# balise_r_ceptrice_-_partie_filtrage.net
KiCad netlist of a schematic drawn in EAGLE
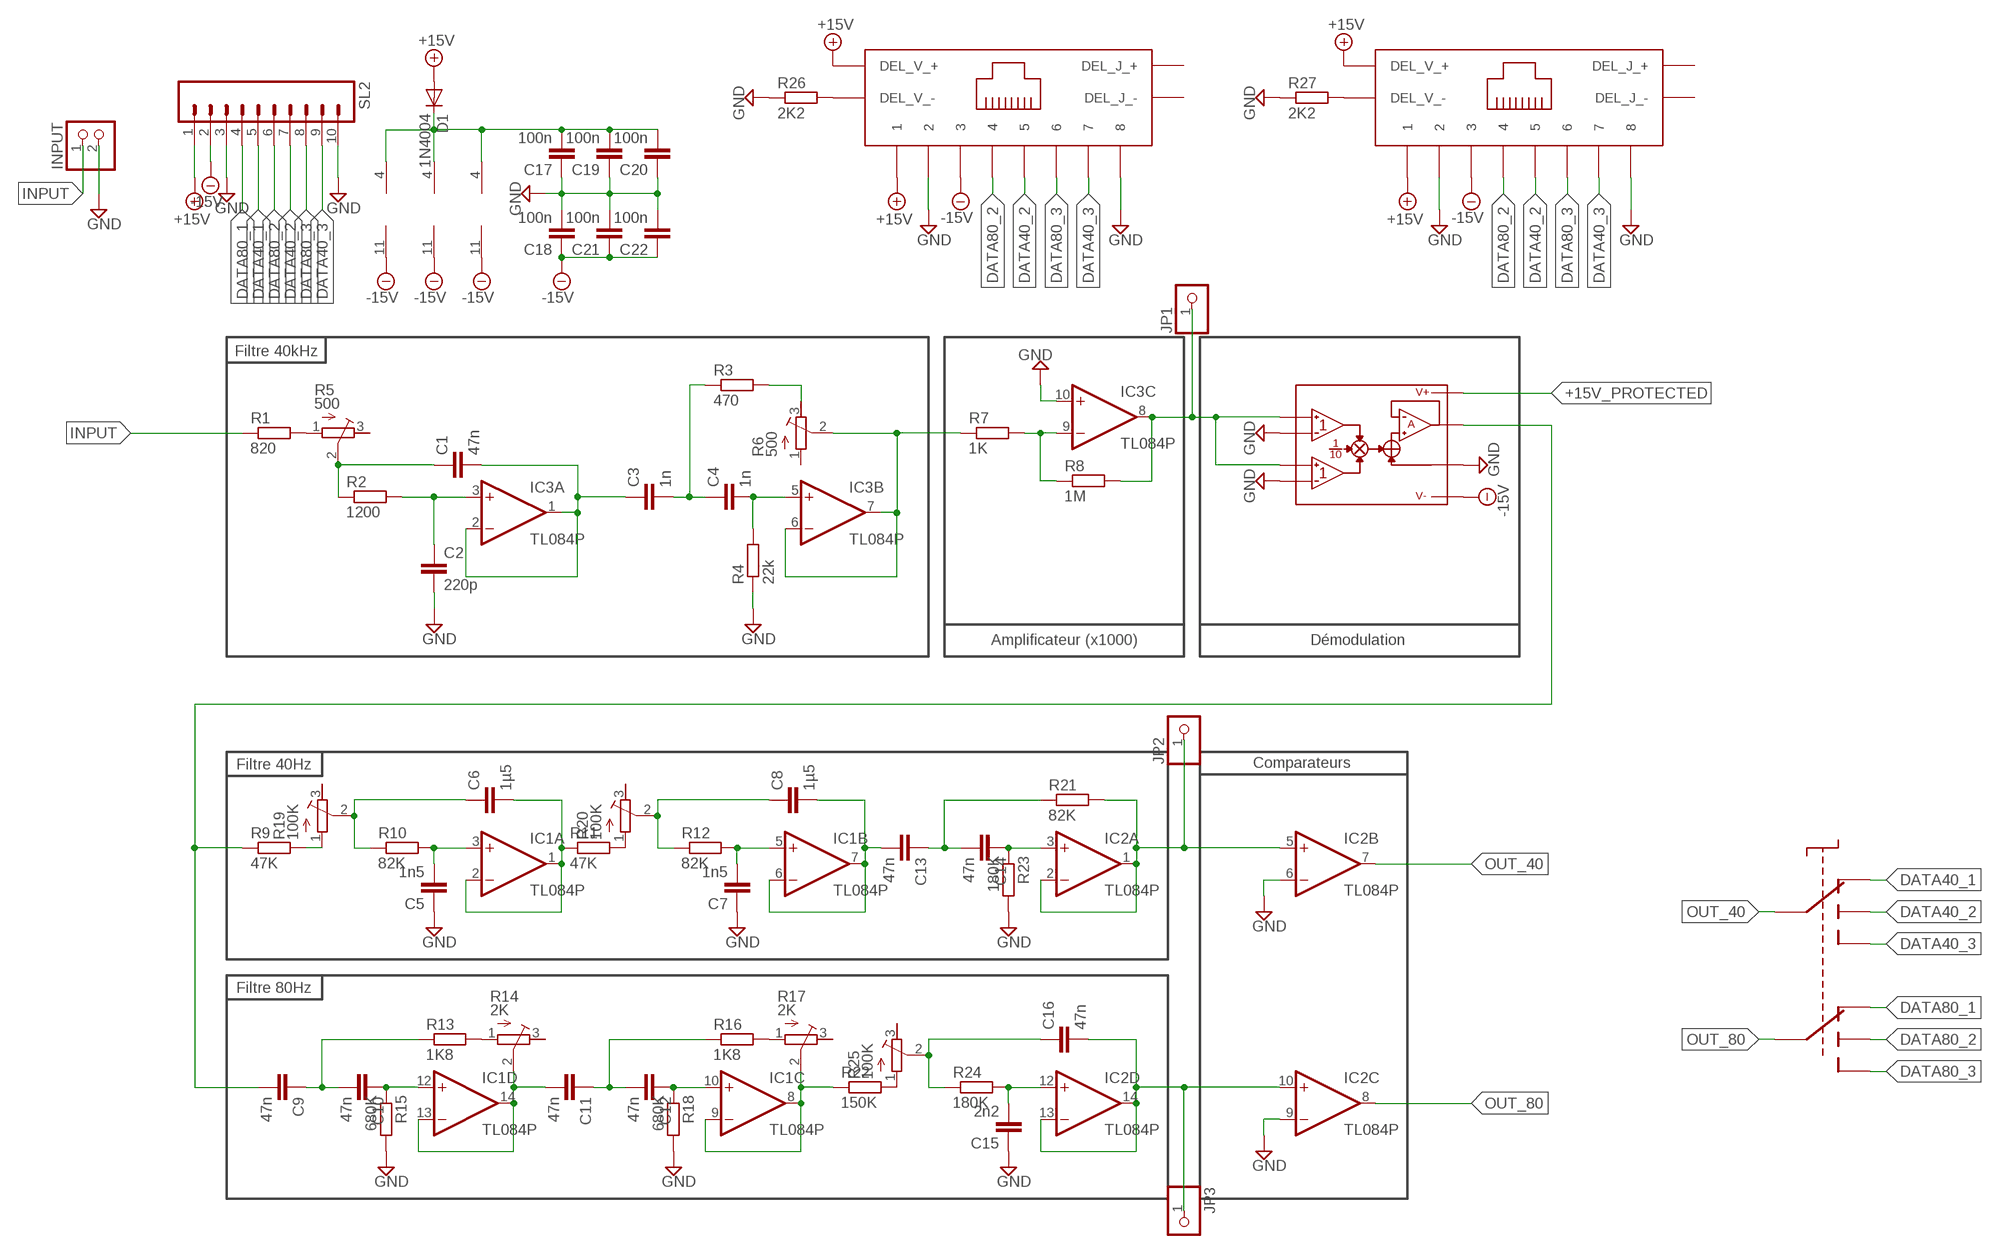
[diagram p0: schematic, sheet 1]

(export (version "E")
  (design (tool "Eeschema 10.0.6"))
  (components
    (comp (ref "C1")
      (value "47n")
      (footprint "eagle-import:C050-024X044")
      (libsource (lib "eagle-import") (part "C-EU050-024X044"))
    )
    (comp (ref "C2")
      (value "220p")
      (footprint "eagle-import:C050-024X044")
      (fields (field (name "MF") "SUSUMU") (field (name "MPN") "RR1220P-104-B-T5"))
      (libsource (lib "eagle-import") (part "C-EU050-024X044"))
    )
    (comp (ref "C3")
      (value "1n")
      (footprint "eagle-import:C050-024X044")
      (libsource (lib "eagle-import") (part "C-EU050-024X044"))
    )
    (comp (ref "C4")
      (value "1n")
      (footprint "eagle-import:C050-024X044")
      (libsource (lib "eagle-import") (part "C-EU050-024X044"))
    )
    (comp (ref "C5")
      (value "1n5")
      (footprint "eagle-import:C050-024X044")
      (libsource (lib "eagle-import") (part "C-EU050-024X044"))
    )
    (comp (ref "C6")
      (value "1µ5")
      (footprint "eagle-import:C150-091X182")
      (libsource (lib "eagle-import") (part "C-EU150-091X182"))
    )
    (comp (ref "C7")
      (value "1n5")
      (footprint "eagle-import:C050-024X044")
      (libsource (lib "eagle-import") (part "C-EU050-024X044"))
    )
    (comp (ref "C8")
      (value "1µ5")
      (footprint "eagle-import:C150-091X182")
      (libsource (lib "eagle-import") (part "C-EU150-091X182"))
    )
    (comp (ref "C9")
      (value "47n")
      (footprint "eagle-import:C050-024X044")
      (libsource (lib "eagle-import") (part "C-EU050-024X044"))
    )
    (comp (ref "C10")
      (value "47n")
      (footprint "eagle-import:C050-024X044")
      (libsource (lib "eagle-import") (part "C-EU050-024X044"))
    )
    (comp (ref "C11")
      (value "47n")
      (footprint "eagle-import:C050-024X044")
      (libsource (lib "eagle-import") (part "C-EU050-024X044"))
    )
    (comp (ref "C12")
      (value "47n")
      (footprint "eagle-import:C050-024X044")
      (libsource (lib "eagle-import") (part "C-EU050-024X044"))
    )
    (comp (ref "C13")
      (value "47n")
      (footprint "eagle-import:C050-024X044")
      (libsource (lib "eagle-import") (part "C-EU050-024X044"))
    )
    (comp (ref "C14")
      (value "47n")
      (footprint "eagle-import:C050-024X044")
      (libsource (lib "eagle-import") (part "C-EU050-024X044"))
    )
    (comp (ref "C15")
      (value "2n2")
      (footprint "eagle-import:C050-024X044")
      (libsource (lib "eagle-import") (part "C-EU050-024X044"))
    )
    (comp (ref "C16")
      (value "47n")
      (footprint "eagle-import:C050-024X044")
      (libsource (lib "eagle-import") (part "C-EU050-024X044"))
    )
    (comp (ref "C17")
      (value "100n")
      (footprint "eagle-import:C050-024X044")
      (libsource (lib "eagle-import") (part "C-EU050-024X044"))
    )
    (comp (ref "C18")
      (value "100n")
      (footprint "eagle-import:C050-024X044")
      (libsource (lib "eagle-import") (part "C-EU050-024X044"))
    )
    (comp (ref "C19")
      (value "100n")
      (footprint "eagle-import:C050-024X044")
      (libsource (lib "eagle-import") (part "C-EU050-024X044"))
    )
    (comp (ref "C20")
      (value "100n")
      (footprint "eagle-import:C050-024X044")
      (libsource (lib "eagle-import") (part "C-EU050-024X044"))
    )
    (comp (ref "C21")
      (value "100n")
      (footprint "eagle-import:C050-024X044")
      (libsource (lib "eagle-import") (part "C-EU050-024X044"))
    )
    (comp (ref "C22")
      (value "100n")
      (footprint "eagle-import:C050-024X044")
      (libsource (lib "eagle-import") (part "C-EU050-024X044"))
    )
    (comp (ref "D1")
      (value "1N4004")
      (footprint "eagle-import:DO41-10")
      (libsource (lib "eagle-import") (part "1N4004"))
    )
    (comp (ref "IC1")
      (value "TL084P")
      (footprint "eagle-import:DIL14")
      (fields (field (name "OC_FARNELL") "unknown"))
      (libsource (lib "eagle-import") (part "TL084P"))
    )
    (comp (ref "IC2")
      (value "TL084P")
      (footprint "eagle-import:DIL14")
      (fields (field (name "OC_FARNELL") "unknown"))
      (libsource (lib "eagle-import") (part "TL084P"))
    )
    (comp (ref "IC3")
      (value "TL084P")
      (footprint "eagle-import:DIL14")
      (fields (field (name "OC_FARNELL") "unknown"))
      (libsource (lib "eagle-import") (part "TL084P"))
    )
    (comp (ref "INPUT")
      (value "PINHD-1X2")
      (footprint "eagle-import:1X02")
      (libsource (lib "eagle-import") (part "PINHD-1X2"))
    )
    (comp (ref "JP1")
      (value "PINHD-1X1")
      (footprint "eagle-import:1X01")
      (libsource (lib "eagle-import") (part "PINHD-1X1"))
    )
    (comp (ref "JP2")
      (value "PINHD-1X1")
      (footprint "eagle-import:1X01")
      (libsource (lib "eagle-import") (part "PINHD-1X1"))
    )
    (comp (ref "JP3")
      (value "PINHD-1X1")
      (footprint "eagle-import:1X01")
      (libsource (lib "eagle-import") (part "PINHD-1X1"))
    )
    (comp (ref "R1")
      (value "820")
      (footprint "eagle-import:0207_2V")
      (libsource (lib "eagle-import") (part "R-EU_0207/2V"))
    )
    (comp (ref "R2")
      (value "1200")
      (footprint "eagle-import:0207_2V")
      (libsource (lib "eagle-import") (part "R-EU_0207/2V"))
    )
    (comp (ref "R3")
      (value "470")
      (footprint "eagle-import:0207_2V")
      (libsource (lib "eagle-import") (part "R-EU_0207/2V"))
    )
    (comp (ref "R4")
      (value "22k")
      (footprint "eagle-import:0207_2V")
      (libsource (lib "eagle-import") (part "R-EU_0207/2V"))
    )
    (comp (ref "R5")
      (value "500")
      (footprint "eagle-import:RTRIM3339P")
      (libsource (lib "eagle-import") (part "R-TRIMM3339P"))
    )
    (comp (ref "R6")
      (value "500")
      (footprint "eagle-import:RTRIM3339P")
      (libsource (lib "eagle-import") (part "R-TRIMM3339P"))
    )
    (comp (ref "R7")
      (value "1K")
      (footprint "eagle-import:0204_7")
      (libsource (lib "eagle-import") (part "R-EU_0204/7"))
    )
    (comp (ref "R8")
      (value "1M")
      (footprint "eagle-import:0204_7")
      (libsource (lib "eagle-import") (part "R-EU_0204/7"))
    )
    (comp (ref "R9")
      (value "47K")
      (footprint "eagle-import:0204_7")
      (libsource (lib "eagle-import") (part "R-EU_0204/7"))
    )
    (comp (ref "R10")
      (value "82K")
      (footprint "eagle-import:0204_7")
      (libsource (lib "eagle-import") (part "R-EU_0204/7"))
    )
    (comp (ref "R11")
      (value "47K")
      (footprint "eagle-import:0207_2V")
      (libsource (lib "eagle-import") (part "R-EU_0207/2V"))
    )
    (comp (ref "R12")
      (value "82K")
      (footprint "eagle-import:0207_2V")
      (libsource (lib "eagle-import") (part "R-EU_0207/2V"))
    )
    (comp (ref "R13")
      (value "1K8")
      (footprint "eagle-import:0207_2V")
      (libsource (lib "eagle-import") (part "R-EU_0207/2V"))
    )
    (comp (ref "R14")
      (value "2K")
      (footprint "eagle-import:RTRIM3339P")
      (libsource (lib "eagle-import") (part "R-TRIMM3339P"))
    )
    (comp (ref "R15")
      (value "680K")
      (footprint "eagle-import:0207_2V")
      (libsource (lib "eagle-import") (part "R-EU_0207/2V"))
    )
    (comp (ref "R16")
      (value "1K8")
      (footprint "eagle-import:0207_2V")
      (libsource (lib "eagle-import") (part "R-EU_0207/2V"))
    )
    (comp (ref "R17")
      (value "2K")
      (footprint "eagle-import:RTRIM3339P")
      (libsource (lib "eagle-import") (part "R-TRIMM3339P"))
    )
    (comp (ref "R18")
      (value "680K")
      (footprint "eagle-import:0207_2V")
      (libsource (lib "eagle-import") (part "R-EU_0207/2V"))
    )
    (comp (ref "R19")
      (value "100K")
      (footprint "eagle-import:RTRIM3339P")
      (libsource (lib "eagle-import") (part "R-TRIMM3339P"))
    )
    (comp (ref "R20")
      (value "100K")
      (footprint "eagle-import:RTRIM3339P")
      (libsource (lib "eagle-import") (part "R-TRIMM3339P"))
    )
    (comp (ref "R21")
      (value "82K")
      (footprint "eagle-import:0207_2V")
      (libsource (lib "eagle-import") (part "R-EU_0207/2V"))
    )
    (comp (ref "R22")
      (value "150K")
      (footprint "eagle-import:0207_2V")
      (libsource (lib "eagle-import") (part "R-EU_0207/2V"))
    )
    (comp (ref "R23")
      (value "180K")
      (footprint "eagle-import:0207_2V")
      (libsource (lib "eagle-import") (part "R-EU_0207/2V"))
    )
    (comp (ref "R24")
      (value "180K")
      (footprint "eagle-import:0207_2V")
      (libsource (lib "eagle-import") (part "R-EU_0207/2V"))
    )
    (comp (ref "R25")
      (value "100K")
      (footprint "eagle-import:RTRIM3339P")
      (libsource (lib "eagle-import") (part "R-TRIMM3339P"))
    )
    (comp (ref "R26")
      (value "2K2")
      (footprint "eagle-import:0207_2V")
      (libsource (lib "eagle-import") (part "R-EU_0207/2V"))
    )
    (comp (ref "R27")
      (value "2K2")
      (footprint "eagle-import:0207_2V")
      (libsource (lib "eagle-import") (part "R-EU_0207/2V"))
    )
    (comp (ref "SL2")
      (value "M10")
      (footprint "eagle-import:10P")
      (fields (field (name "OC_FARNELL") "unknown"))
      (libsource (lib "eagle-import") (part "M10"))
    )
    (comp (ref "U$1")
      (value "AD633JN")
      (footprint "eagle-import:DIL08")
      (libsource (lib "eagle-import") (part "AD633JN"))
    )
    (comp (ref "U$2")
      (value "RJ45_FEMELLE")
      (footprint "eagle-import:RJ45_FEMELLE")
      (libsource (lib "eagle-import") (part "RJ45_FEMELLE"))
    )
    (comp (ref "U$3")
      (value "RJ45_FEMELLE")
      (footprint "eagle-import:RJ45_FEMELLE")
      (libsource (lib "eagle-import") (part "RJ45_FEMELLE"))
    )
    (comp (ref "U$4")
      (value "SWITCH_DP3T_SP112")
      (footprint "eagle-import:SWITCH_SP112")
      (libsource (lib "eagle-import") (part "SWITCH_DP3T_SP112"))
    )
  )
  (nets
    (net (code "1") (name "+15V") (class "Default")
      (node (ref "D1") (pin "A") (pinfunction "A_A") (pintype "passive"))
      (node (ref "SL2") (pin "1") (pinfunction "1_1") (pintype "passive"))
      (node (ref "U$2") (pin "1") (pinfunction "1_1") (pintype "bidirectional"))
      (node (ref "U$2") (pin "DEL_V_+") (pinfunction "DEL_V_+_DEL_V_+") (pintype "bidirectional"))
      (node (ref "U$3") (pin "1") (pinfunction "1_1") (pintype "bidirectional"))
      (node (ref "U$3") (pin "DEL_V_+") (pinfunction "DEL_V_+_DEL_V_+") (pintype "bidirectional"))
    )
    (net (code "2") (name "+15V_PROTECTED") (class "Default")
      (node (ref "C17") (pin "2") (pinfunction "2_2") (pintype "passive"))
      (node (ref "C19") (pin "2") (pinfunction "2_2") (pintype "passive"))
      (node (ref "C20") (pin "2") (pinfunction "2_2") (pintype "passive"))
      (node (ref "D1") (pin "C") (pinfunction "C_C") (pintype "passive"))
      (node (ref "IC1") (pin "4") (pinfunction "V+_4") (pintype "power_in"))
      (node (ref "IC2") (pin "4") (pinfunction "V+_4") (pintype "power_in"))
      (node (ref "IC3") (pin "4") (pinfunction "V+_4") (pintype "power_in"))
      (node (ref "U$1") (pin "8") (pinfunction "+V_8") (pintype "bidirectional"))
    )
    (net (code "3") (name "-15V") (class "Default")
      (node (ref "C18") (pin "1") (pinfunction "1_1") (pintype "passive"))
      (node (ref "C21") (pin "1") (pinfunction "1_1") (pintype "passive"))
      (node (ref "C22") (pin "1") (pinfunction "1_1") (pintype "passive"))
      (node (ref "IC1") (pin "11") (pinfunction "V-_11") (pintype "power_in"))
      (node (ref "IC2") (pin "11") (pinfunction "V-_11") (pintype "power_in"))
      (node (ref "IC3") (pin "11") (pinfunction "V-_11") (pintype "power_in"))
      (node (ref "SL2") (pin "2") (pinfunction "2_2") (pintype "passive"))
      (node (ref "U$1") (pin "5") (pinfunction "-V_5") (pintype "bidirectional"))
      (node (ref "U$2") (pin "3") (pinfunction "3_3") (pintype "bidirectional"))
      (node (ref "U$3") (pin "3") (pinfunction "3_3") (pintype "bidirectional"))
    )
    (net (code "4") (name "DATA40_1") (class "Default")
      (node (ref "SL2") (pin "5") (pinfunction "5_5") (pintype "passive"))
      (node (ref "U$4") (pin "1A") (pinfunction "1A_1A") (pintype "bidirectional"))
    )
    (net (code "5") (name "DATA40_2") (class "Default")
      (node (ref "SL2") (pin "7") (pinfunction "7_7") (pintype "passive"))
      (node (ref "U$2") (pin "5") (pinfunction "5_5") (pintype "bidirectional"))
      (node (ref "U$3") (pin "5") (pinfunction "5_5") (pintype "bidirectional"))
      (node (ref "U$4") (pin "1B") (pinfunction "1B_1B") (pintype "bidirectional"))
    )
    (net (code "6") (name "DATA40_3") (class "Default")
      (node (ref "SL2") (pin "9") (pinfunction "9_9") (pintype "passive"))
      (node (ref "U$2") (pin "7") (pinfunction "7_7") (pintype "bidirectional"))
      (node (ref "U$3") (pin "7") (pinfunction "7_7") (pintype "bidirectional"))
      (node (ref "U$4") (pin "1C") (pinfunction "1C_1C") (pintype "bidirectional"))
    )
    (net (code "7") (name "DATA80_1") (class "Default")
      (node (ref "SL2") (pin "4") (pinfunction "4_4") (pintype "passive"))
      (node (ref "U$4") (pin "2A") (pinfunction "2A_2A") (pintype "bidirectional"))
    )
    (net (code "8") (name "DATA80_2") (class "Default")
      (node (ref "SL2") (pin "6") (pinfunction "6_6") (pintype "passive"))
      (node (ref "U$2") (pin "4") (pinfunction "4_4") (pintype "bidirectional"))
      (node (ref "U$3") (pin "4") (pinfunction "4_4") (pintype "bidirectional"))
      (node (ref "U$4") (pin "2B") (pinfunction "2B_2B") (pintype "bidirectional"))
    )
    (net (code "9") (name "DATA80_3") (class "Default")
      (node (ref "SL2") (pin "8") (pinfunction "8_8") (pintype "passive"))
      (node (ref "U$2") (pin "6") (pinfunction "6_6") (pintype "bidirectional"))
      (node (ref "U$3") (pin "6") (pinfunction "6_6") (pintype "bidirectional"))
      (node (ref "U$4") (pin "2C") (pinfunction "2C_2C") (pintype "bidirectional"))
    )
    (net (code "10") (name "GND") (class "Default")
      (node (ref "C15") (pin "1") (pinfunction "1_1") (pintype "passive"))
      (node (ref "C17") (pin "1") (pinfunction "1_1") (pintype "passive"))
      (node (ref "C18") (pin "2") (pinfunction "2_2") (pintype "passive"))
      (node (ref "C19") (pin "1") (pinfunction "1_1") (pintype "passive"))
      (node (ref "C2") (pin "2") (pinfunction "2_2") (pintype "passive"))
      (node (ref "C20") (pin "1") (pinfunction "1_1") (pintype "passive"))
      (node (ref "C21") (pin "2") (pinfunction "2_2") (pintype "passive"))
      (node (ref "C22") (pin "2") (pinfunction "2_2") (pintype "passive"))
      (node (ref "C5") (pin "1") (pinfunction "1_1") (pintype "passive"))
      (node (ref "C7") (pin "1") (pinfunction "1_1") (pintype "passive"))
      (node (ref "IC2") (pin "6") (pinfunction "-IN_6") (pintype "input"))
      (node (ref "IC2") (pin "9") (pinfunction "-IN_9") (pintype "input"))
      (node (ref "IC3") (pin "10") (pinfunction "+IN_10") (pintype "input"))
      (node (ref "INPUT") (pin "2") (pinfunction "2_2") (pintype "passive"))
      (node (ref "R15") (pin "2") (pinfunction "2_2") (pintype "passive"))
      (node (ref "R18") (pin "2") (pinfunction "2_2") (pintype "passive"))
      (node (ref "R23") (pin "2") (pinfunction "2_2") (pintype "passive"))
      (node (ref "R26") (pin "1") (pinfunction "1_1") (pintype "passive"))
      (node (ref "R27") (pin "1") (pinfunction "1_1") (pintype "passive"))
      (node (ref "R4") (pin "1") (pinfunction "1_1") (pintype "passive"))
      (node (ref "SL2") (pin "10") (pinfunction "10_10") (pintype "passive"))
      (node (ref "SL2") (pin "3") (pinfunction "3_3") (pintype "passive"))
      (node (ref "U$1") (pin "2") (pinfunction "X2_2") (pintype "bidirectional"))
      (node (ref "U$1") (pin "4") (pinfunction "Y2_4") (pintype "bidirectional"))
      (node (ref "U$1") (pin "6") (pinfunction "Z_6") (pintype "bidirectional"))
      (node (ref "U$2") (pin "2") (pinfunction "2_2") (pintype "bidirectional"))
      (node (ref "U$2") (pin "8") (pinfunction "8_8") (pintype "bidirectional"))
      (node (ref "U$3") (pin "2") (pinfunction "2_2") (pintype "bidirectional"))
      (node (ref "U$3") (pin "8") (pinfunction "8_8") (pintype "bidirectional"))
    )
    (net (code "11") (name "INPUT") (class "Default")
      (node (ref "INPUT") (pin "1") (pinfunction "1_1") (pintype "passive"))
      (node (ref "R1") (pin "1") (pinfunction "1_1") (pintype "passive"))
    )
    (net (code "12") (name "Net-(C3-Pad2)") (class "Default")
      (node (ref "C3") (pin "2") (pinfunction "2_2") (pintype "passive"))
      (node (ref "C4") (pin "1") (pinfunction "1_1") (pintype "passive"))
      (node (ref "R3") (pin "1") (pinfunction "1_1") (pintype "passive"))
    )
    (net (code "13") (name "Net-(C10-Pad2)") (class "Default")
      (node (ref "C10") (pin "2") (pinfunction "2_2") (pintype "passive"))
      (node (ref "C9") (pin "1") (pinfunction "1_1") (pintype "passive"))
      (node (ref "R13") (pin "1") (pinfunction "1_1") (pintype "passive"))
    )
    (net (code "14") (name "Net-(C11-Pad1)") (class "Default")
      (node (ref "C11") (pin "1") (pinfunction "1_1") (pintype "passive"))
      (node (ref "C12") (pin "2") (pinfunction "2_2") (pintype "passive"))
      (node (ref "R16") (pin "1") (pinfunction "1_1") (pintype "passive"))
    )
    (net (code "15") (name "Net-(C13-Pad1)") (class "Default")
      (node (ref "C13") (pin "1") (pinfunction "1_1") (pintype "passive"))
      (node (ref "C14") (pin "2") (pinfunction "2_2") (pintype "passive"))
      (node (ref "R21") (pin "1") (pinfunction "1_1") (pintype "passive"))
    )
    (net (code "16") (name "Net-(IC1A-+IN)") (class "Default")
      (node (ref "C5") (pin "2") (pinfunction "2_2") (pintype "passive"))
      (node (ref "IC1") (pin "3") (pinfunction "+IN_3") (pintype "input"))
      (node (ref "R10") (pin "2") (pinfunction "2_2") (pintype "passive"))
    )
    (net (code "17") (name "Net-(IC1A--IN)") (class "Default")
      (node (ref "C6") (pin "2") (pinfunction "2_2") (pintype "passive"))
      (node (ref "IC1") (pin "1") (pinfunction "OUT_1") (pintype "output"))
      (node (ref "IC1") (pin "2") (pinfunction "-IN_2") (pintype "input"))
      (node (ref "R11") (pin "1") (pinfunction "1_1") (pintype "passive"))
    )
    (net (code "18") (name "Net-(IC1B-+IN)") (class "Default")
      (node (ref "C7") (pin "2") (pinfunction "2_2") (pintype "passive"))
      (node (ref "IC1") (pin "5") (pinfunction "+IN_5") (pintype "input"))
      (node (ref "R12") (pin "2") (pinfunction "2_2") (pintype "passive"))
    )
    (net (code "19") (name "Net-(IC1B--IN)") (class "Default")
      (node (ref "C13") (pin "2") (pinfunction "2_2") (pintype "passive"))
      (node (ref "C8") (pin "2") (pinfunction "2_2") (pintype "passive"))
      (node (ref "IC1") (pin "6") (pinfunction "-IN_6") (pintype "input"))
      (node (ref "IC1") (pin "7") (pinfunction "OUT_7") (pintype "output"))
    )
    (net (code "20") (name "Net-(IC1C-+IN)") (class "Default")
      (node (ref "C12") (pin "1") (pinfunction "1_1") (pintype "passive"))
      (node (ref "IC1") (pin "10") (pinfunction "+IN_10") (pintype "input"))
      (node (ref "R18") (pin "1") (pinfunction "1_1") (pintype "passive"))
    )
    (net (code "21") (name "Net-(IC1C--IN)") (class "Default")
      (node (ref "IC1") (pin "8") (pinfunction "OUT_8") (pintype "output"))
      (node (ref "IC1") (pin "9") (pinfunction "-IN_9") (pintype "input"))
      (node (ref "R17") (pin "2") (pinfunction "S_2") (pintype "passive"))
      (node (ref "R22") (pin "1") (pinfunction "1_1") (pintype "passive"))
    )
    (net (code "22") (name "Net-(IC1D-+IN)") (class "Default")
      (node (ref "C10") (pin "1") (pinfunction "1_1") (pintype "passive"))
      (node (ref "IC1") (pin "12") (pinfunction "+IN_12") (pintype "input"))
      (node (ref "R15") (pin "1") (pinfunction "1_1") (pintype "passive"))
    )
    (net (code "23") (name "Net-(IC1D--IN)") (class "Default")
      (node (ref "C11") (pin "2") (pinfunction "2_2") (pintype "passive"))
      (node (ref "IC1") (pin "13") (pinfunction "-IN_13") (pintype "input"))
      (node (ref "IC1") (pin "14") (pinfunction "OUT_14") (pintype "output"))
      (node (ref "R14") (pin "2") (pinfunction "S_2") (pintype "passive"))
    )
    (net (code "24") (name "Net-(IC2A-+IN)") (class "Default")
      (node (ref "C14") (pin "1") (pinfunction "1_1") (pintype "passive"))
      (node (ref "IC2") (pin "3") (pinfunction "+IN_3") (pintype "input"))
      (node (ref "R23") (pin "1") (pinfunction "1_1") (pintype "passive"))
    )
    (net (code "25") (name "Net-(IC2A--IN)") (class "Default")
      (node (ref "IC2") (pin "1") (pinfunction "OUT_1") (pintype "output"))
      (node (ref "IC2") (pin "2") (pinfunction "-IN_2") (pintype "input"))
      (node (ref "IC2") (pin "5") (pinfunction "+IN_5") (pintype "input"))
      (node (ref "JP2") (pin "1") (pinfunction "1_1") (pintype "passive"))
      (node (ref "R21") (pin "2") (pinfunction "2_2") (pintype "passive"))
    )
    (net (code "26") (name "Net-(IC2C-+IN)") (class "Default")
      (node (ref "C16") (pin "2") (pinfunction "2_2") (pintype "passive"))
      (node (ref "IC2") (pin "10") (pinfunction "+IN_10") (pintype "input"))
      (node (ref "IC2") (pin "13") (pinfunction "-IN_13") (pintype "input"))
      (node (ref "IC2") (pin "14") (pinfunction "OUT_14") (pintype "output"))
      (node (ref "JP3") (pin "1") (pinfunction "1_1") (pintype "passive"))
    )
    (net (code "27") (name "Net-(IC2D-+IN)") (class "Default")
      (node (ref "C15") (pin "2") (pinfunction "2_2") (pintype "passive"))
      (node (ref "IC2") (pin "12") (pinfunction "+IN_12") (pintype "input"))
      (node (ref "R24") (pin "2") (pinfunction "2_2") (pintype "passive"))
    )
    (net (code "28") (name "Net-(IC3A-+IN)") (class "Default")
      (node (ref "C2") (pin "1") (pinfunction "1_1") (pintype "passive"))
      (node (ref "IC3") (pin "3") (pinfunction "+IN_3") (pintype "input"))
      (node (ref "R2") (pin "2") (pinfunction "2_2") (pintype "passive"))
    )
    (net (code "29") (name "Net-(IC3A--IN)") (class "Default")
      (node (ref "C1") (pin "2") (pinfunction "2_2") (pintype "passive"))
      (node (ref "C3") (pin "1") (pinfunction "1_1") (pintype "passive"))
      (node (ref "IC3") (pin "1") (pinfunction "OUT_1") (pintype "output"))
      (node (ref "IC3") (pin "2") (pinfunction "-IN_2") (pintype "input"))
    )
    (net (code "30") (name "Net-(IC3B-+IN)") (class "Default")
      (node (ref "C4") (pin "2") (pinfunction "2_2") (pintype "passive"))
      (node (ref "IC3") (pin "5") (pinfunction "+IN_5") (pintype "input"))
      (node (ref "R4") (pin "2") (pinfunction "2_2") (pintype "passive"))
    )
    (net (code "31") (name "Net-(IC3B--IN)") (class "Default")
      (node (ref "IC3") (pin "6") (pinfunction "-IN_6") (pintype "input"))
      (node (ref "IC3") (pin "7") (pinfunction "OUT_7") (pintype "output"))
      (node (ref "R6") (pin "2") (pinfunction "S_2") (pintype "passive"))
      (node (ref "R7") (pin "1") (pinfunction "1_1") (pintype "passive"))
    )
    (net (code "32") (name "Net-(IC3C--IN)") (class "Default")
      (node (ref "IC3") (pin "9") (pinfunction "-IN_9") (pintype "input"))
      (node (ref "R7") (pin "2") (pinfunction "2_2") (pintype "passive"))
      (node (ref "R8") (pin "1") (pinfunction "1_1") (pintype "passive"))
    )
    (net (code "33") (name "Net-(IC3C-OUT)") (class "Default")
      (node (ref "IC3") (pin "8") (pinfunction "OUT_8") (pintype "output"))
      (node (ref "JP1") (pin "1") (pinfunction "1_1") (pintype "passive"))
      (node (ref "R8") (pin "2") (pinfunction "2_2") (pintype "passive"))
      (node (ref "U$1") (pin "1") (pinfunction "X1_1") (pintype "bidirectional"))
      (node (ref "U$1") (pin "3") (pinfunction "Y1_3") (pintype "bidirectional"))
    )
    (net (code "34") (name "Net-(R5-E)") (class "Default")
      (node (ref "R1") (pin "2") (pinfunction "2_2") (pintype "passive"))
      (node (ref "R5") (pin "1") (pinfunction "E_1") (pintype "passive"))
    )
    (net (code "35") (name "Net-(R5-S)") (class "Default")
      (node (ref "C1") (pin "1") (pinfunction "1_1") (pintype "passive"))
      (node (ref "R2") (pin "1") (pinfunction "1_1") (pintype "passive"))
      (node (ref "R5") (pin "2") (pinfunction "S_2") (pintype "passive"))
    )
    (net (code "36") (name "Net-(R6-A)") (class "Default")
      (node (ref "R3") (pin "2") (pinfunction "2_2") (pintype "passive"))
      (node (ref "R6") (pin "3") (pinfunction "A_3") (pintype "passive"))
    )
    (net (code "37") (name "Net-(R14-E)") (class "Default")
      (node (ref "R13") (pin "2") (pinfunction "2_2") (pintype "passive"))
      (node (ref "R14") (pin "1") (pinfunction "E_1") (pintype "passive"))
    )
    (net (code "38") (name "Net-(R17-E)") (class "Default")
      (node (ref "R16") (pin "2") (pinfunction "2_2") (pintype "passive"))
      (node (ref "R17") (pin "1") (pinfunction "E_1") (pintype "passive"))
    )
    (net (code "39") (name "Net-(R19-E)") (class "Default")
      (node (ref "R19") (pin "1") (pinfunction "E_1") (pintype "passive"))
      (node (ref "R9") (pin "2") (pinfunction "2_2") (pintype "passive"))
    )
    (net (code "40") (name "Net-(R19-S)") (class "Default")
      (node (ref "C6") (pin "1") (pinfunction "1_1") (pintype "passive"))
      (node (ref "R10") (pin "1") (pinfunction "1_1") (pintype "passive"))
      (node (ref "R19") (pin "2") (pinfunction "S_2") (pintype "passive"))
    )
    (net (code "41") (name "Net-(R20-E)") (class "Default")
      (node (ref "R11") (pin "2") (pinfunction "2_2") (pintype "passive"))
      (node (ref "R20") (pin "1") (pinfunction "E_1") (pintype "passive"))
    )
    (net (code "42") (name "Net-(R20-S)") (class "Default")
      (node (ref "C8") (pin "1") (pinfunction "1_1") (pintype "passive"))
      (node (ref "R12") (pin "1") (pinfunction "1_1") (pintype "passive"))
      (node (ref "R20") (pin "2") (pinfunction "S_2") (pintype "passive"))
    )
    (net (code "43") (name "Net-(R25-E)") (class "Default")
      (node (ref "R22") (pin "2") (pinfunction "2_2") (pintype "passive"))
      (node (ref "R25") (pin "1") (pinfunction "E_1") (pintype "passive"))
    )
    (net (code "44") (name "Net-(R25-S)") (class "Default")
      (node (ref "C16") (pin "1") (pinfunction "1_1") (pintype "passive"))
      (node (ref "R24") (pin "1") (pinfunction "1_1") (pintype "passive"))
      (node (ref "R25") (pin "2") (pinfunction "S_2") (pintype "passive"))
    )
    (net (code "45") (name "Net-(R26-Pad2)") (class "Default")
      (node (ref "R26") (pin "2") (pinfunction "2_2") (pintype "passive"))
      (node (ref "U$2") (pin "DEL_V_-") (pinfunction "DEL_V_-_DEL_V_-") (pintype "bidirectional"))
    )
    (net (code "46") (name "Net-(R27-Pad2)") (class "Default")
      (node (ref "R27") (pin "2") (pinfunction "2_2") (pintype "passive"))
      (node (ref "U$3") (pin "DEL_V_-") (pinfunction "DEL_V_-_DEL_V_-") (pintype "bidirectional"))
    )
    (net (code "47") (name "Net-(U$1-W)") (class "Default")
      (node (ref "C9") (pin "2") (pinfunction "2_2") (pintype "passive"))
      (node (ref "R9") (pin "1") (pinfunction "1_1") (pintype "passive"))
      (node (ref "U$1") (pin "7") (pinfunction "W_7") (pintype "bidirectional"))
    )
    (net (code "48") (name "OUT_40") (class "Default")
      (node (ref "IC2") (pin "7") (pinfunction "OUT_7") (pintype "output"))
      (node (ref "U$4") (pin "COM_1") (pinfunction "COM1_COM_1") (pintype "bidirectional"))
    )
    (net (code "49") (name "OUT_80") (class "Default")
      (node (ref "IC2") (pin "8") (pinfunction "OUT_8") (pintype "output"))
      (node (ref "U$4") (pin "COM_2") (pinfunction "COM2_COM_2") (pintype "bidirectional"))
    )
    (net (code "50") (name "unconnected-(R5-A-Pad3)") (class "Default")
      (node (ref "R5") (pin "3") (pinfunction "A_3") (pintype "passive"))
    )
    (net (code "51") (name "unconnected-(R6-E-Pad1)") (class "Default")
      (node (ref "R6") (pin "1") (pinfunction "E_1") (pintype "passive"))
    )
    (net (code "52") (name "unconnected-(R14-A-Pad3)") (class "Default")
      (node (ref "R14") (pin "3") (pinfunction "A_3") (pintype "passive"))
    )
    (net (code "53") (name "unconnected-(R17-A-Pad3)") (class "Default")
      (node (ref "R17") (pin "3") (pinfunction "A_3") (pintype "passive"))
    )
    (net (code "54") (name "unconnected-(R19-A-Pad3)") (class "Default")
      (node (ref "R19") (pin "3") (pinfunction "A_3") (pintype "passive"))
    )
    (net (code "55") (name "unconnected-(R20-A-Pad3)") (class "Default")
      (node (ref "R20") (pin "3") (pinfunction "A_3") (pintype "passive"))
    )
    (net (code "56") (name "unconnected-(R25-A-Pad3)") (class "Default")
      (node (ref "R25") (pin "3") (pinfunction "A_3") (pintype "passive"))
    )
    (net (code "57") (name "unconnected-(U$2-PadDEL_J_+)") (class "Default")
      (node (ref "U$2") (pin "DEL_J_+") (pinfunction "DEL_J_+_DEL_J_+") (pintype "bidirectional"))
    )
    (net (code "58") (name "unconnected-(U$2-PadDEL_J_-)") (class "Default")
      (node (ref "U$2") (pin "DEL_J_-") (pinfunction "DEL_J_-_DEL_J_-") (pintype "bidirectional"))
    )
    (net (code "59") (name "unconnected-(U$3-PadDEL_J_+)") (class "Default")
      (node (ref "U$3") (pin "DEL_J_+") (pinfunction "DEL_J_+_DEL_J_+") (pintype "bidirectional"))
    )
    (net (code "60") (name "unconnected-(U$3-PadDEL_J_-)") (class "Default")
      (node (ref "U$3") (pin "DEL_J_-") (pinfunction "DEL_J_-_DEL_J_-") (pintype "bidirectional"))
    )
  )
)
